# p128relay.net
KiCad netlist of a schematic drawn in EAGLE
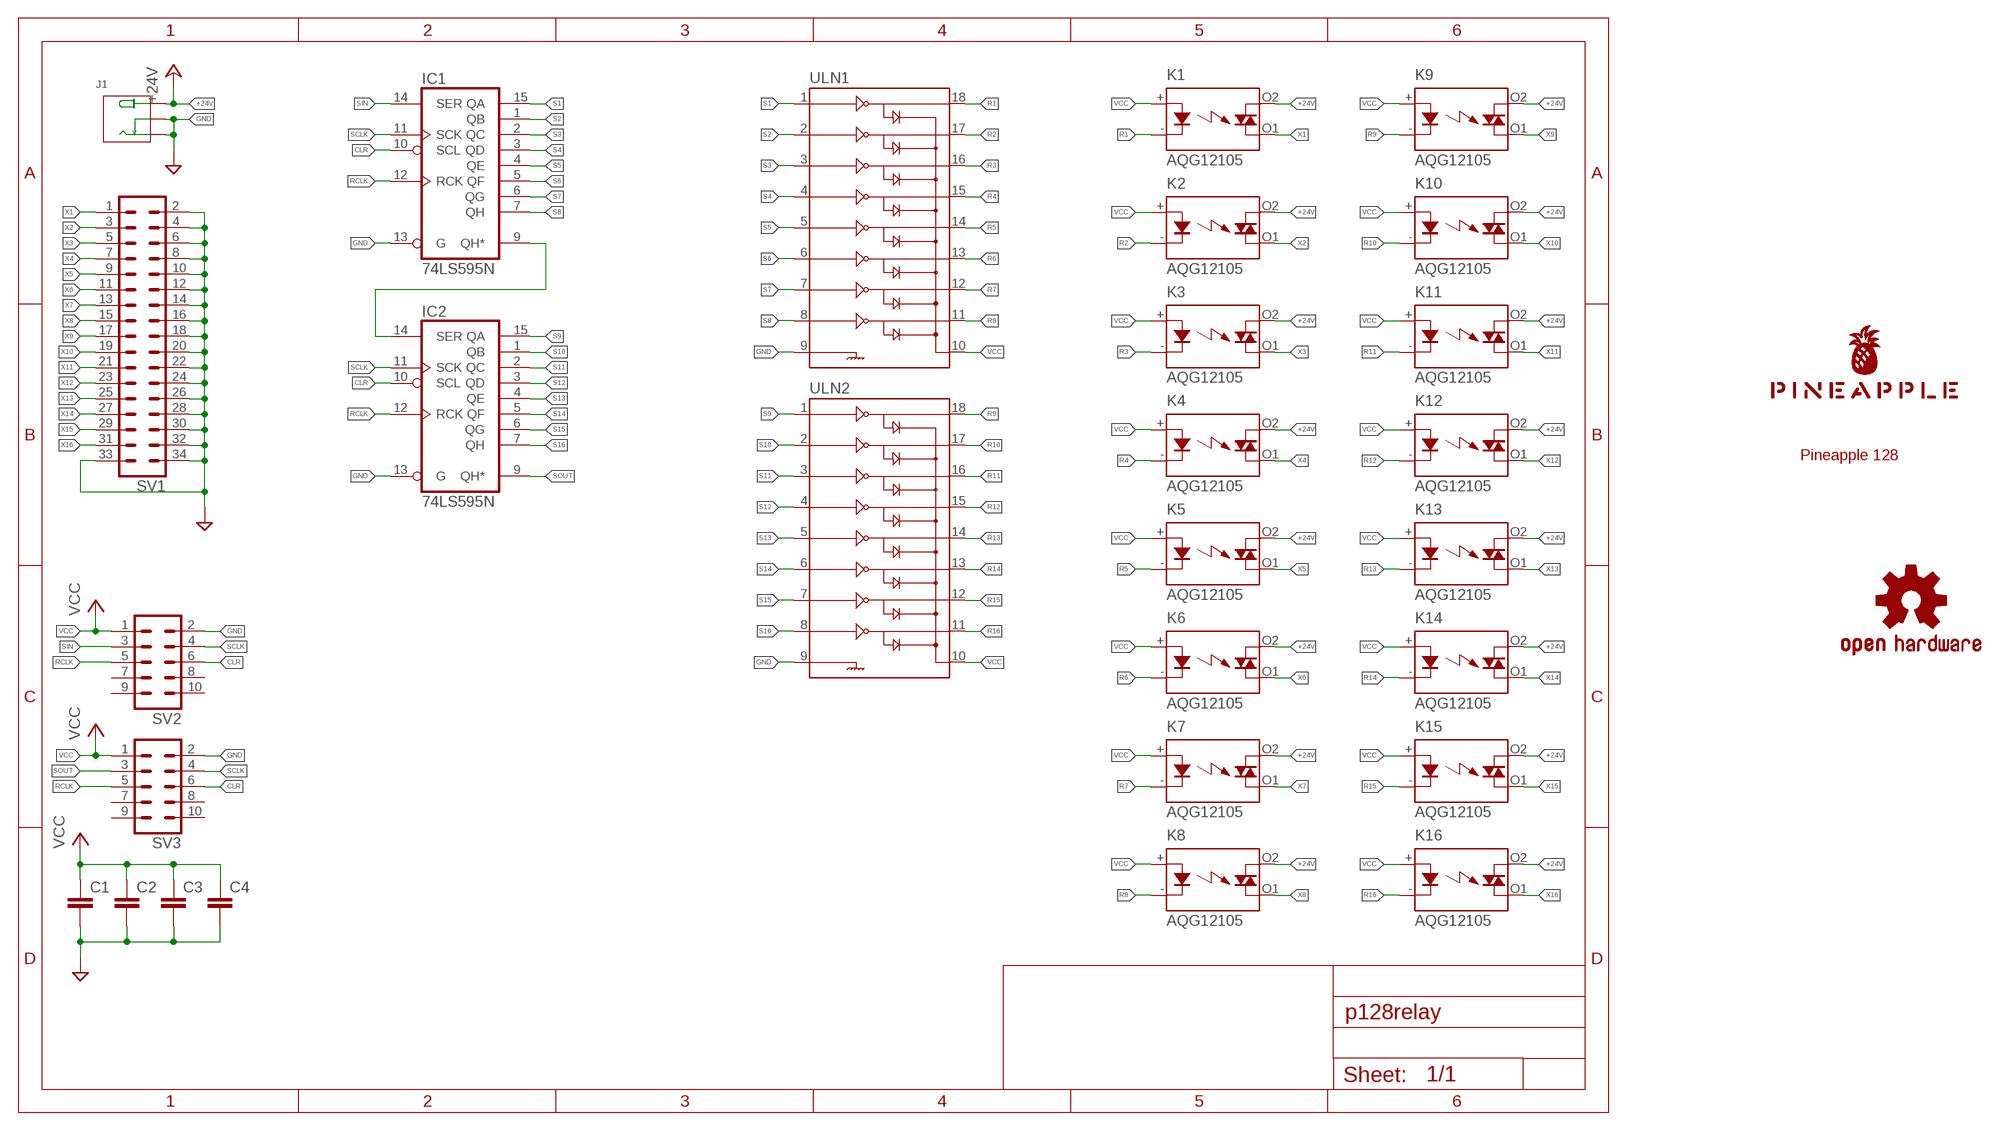
[diagram p0: schematic, sheet 1]

(export (version "E")
  (design (tool "Eeschema 10.0.6"))
  (components
    (comp (ref "C1")
      (value "C-EU025-024X044")
      (footprint "eagle-import:C025-024X044")
      (libsource (lib "eagle-import") (part "C-EU025-024X044"))
    )
    (comp (ref "C2")
      (value "C-EU025-024X044")
      (footprint "eagle-import:C025-024X044")
      (libsource (lib "eagle-import") (part "C-EU025-024X044"))
    )
    (comp (ref "C3")
      (value "C-EU025-024X044")
      (footprint "eagle-import:C025-024X044")
      (libsource (lib "eagle-import") (part "C-EU025-024X044"))
    )
    (comp (ref "C4")
      (value "C-EU025-024X044")
      (footprint "eagle-import:C025-024X044")
      (libsource (lib "eagle-import") (part "C-EU025-024X044"))
    )
    (comp (ref "IC1")
      (value "74LS595N")
      (footprint "eagle-import:DIL16")
      (libsource (lib "eagle-import") (part "74595NLS"))
    )
    (comp (ref "IC2")
      (value "74LS595N")
      (footprint "eagle-import:DIL16")
      (libsource (lib "eagle-import") (part "74595NLS"))
    )
    (comp (ref "J1")
      (value "JACK-DC-005'DC-005'")
      (footprint "eagle-import:3P-L14.2_W11.0_H9.0MM")
      (libsource (lib "eagle-import") (part "JACK-DC-005'DC-005'"))
    )
    (comp (ref "K1")
      (value "AQG12105")
      (footprint "eagle-import:AQG")
      (fields (field (name "MF") "AROMAT/ MATSUSHITA"))
      (libsource (lib "eagle-import") (part "AQG12105"))
    )
    (comp (ref "K2")
      (value "AQG12105")
      (footprint "eagle-import:AQG")
      (fields (field (name "MF") "AROMAT/ MATSUSHITA"))
      (libsource (lib "eagle-import") (part "AQG12105"))
    )
    (comp (ref "K3")
      (value "AQG12105")
      (footprint "eagle-import:AQG")
      (fields (field (name "MF") "AROMAT/ MATSUSHITA"))
      (libsource (lib "eagle-import") (part "AQG12105"))
    )
    (comp (ref "K4")
      (value "AQG12105")
      (footprint "eagle-import:AQG")
      (fields (field (name "MF") "AROMAT/ MATSUSHITA"))
      (libsource (lib "eagle-import") (part "AQG12105"))
    )
    (comp (ref "K5")
      (value "AQG12105")
      (footprint "eagle-import:AQG")
      (fields (field (name "MF") "AROMAT/ MATSUSHITA"))
      (libsource (lib "eagle-import") (part "AQG12105"))
    )
    (comp (ref "K6")
      (value "AQG12105")
      (footprint "eagle-import:AQG")
      (fields (field (name "MF") "AROMAT/ MATSUSHITA"))
      (libsource (lib "eagle-import") (part "AQG12105"))
    )
    (comp (ref "K7")
      (value "AQG12105")
      (footprint "eagle-import:AQG")
      (fields (field (name "MF") "AROMAT/ MATSUSHITA"))
      (libsource (lib "eagle-import") (part "AQG12105"))
    )
    (comp (ref "K8")
      (value "AQG12105")
      (footprint "eagle-import:AQG")
      (fields (field (name "MF") "AROMAT/ MATSUSHITA"))
      (libsource (lib "eagle-import") (part "AQG12105"))
    )
    (comp (ref "K9")
      (value "AQG12105")
      (footprint "eagle-import:AQG")
      (fields (field (name "MF") "AROMAT/ MATSUSHITA"))
      (libsource (lib "eagle-import") (part "AQG12105"))
    )
    (comp (ref "K10")
      (value "AQG12105")
      (footprint "eagle-import:AQG")
      (fields (field (name "MF") "AROMAT/ MATSUSHITA"))
      (libsource (lib "eagle-import") (part "AQG12105"))
    )
    (comp (ref "K11")
      (value "AQG12105")
      (footprint "eagle-import:AQG")
      (fields (field (name "MF") "AROMAT/ MATSUSHITA"))
      (libsource (lib "eagle-import") (part "AQG12105"))
    )
    (comp (ref "K12")
      (value "AQG12105")
      (footprint "eagle-import:AQG")
      (fields (field (name "MF") "AROMAT/ MATSUSHITA"))
      (libsource (lib "eagle-import") (part "AQG12105"))
    )
    (comp (ref "K13")
      (value "AQG12105")
      (footprint "eagle-import:AQG")
      (fields (field (name "MF") "AROMAT/ MATSUSHITA"))
      (libsource (lib "eagle-import") (part "AQG12105"))
    )
    (comp (ref "K14")
      (value "AQG12105")
      (footprint "eagle-import:AQG")
      (fields (field (name "MF") "AROMAT/ MATSUSHITA"))
      (libsource (lib "eagle-import") (part "AQG12105"))
    )
    (comp (ref "K15")
      (value "AQG12105")
      (footprint "eagle-import:AQG")
      (fields (field (name "MF") "AROMAT/ MATSUSHITA"))
      (libsource (lib "eagle-import") (part "AQG12105"))
    )
    (comp (ref "K16")
      (value "AQG12105")
      (footprint "eagle-import:AQG")
      (fields (field (name "MF") "AROMAT/ MATSUSHITA"))
      (libsource (lib "eagle-import") (part "AQG12105"))
    )
    (comp (ref "LOGO1")
      (value "OSHW-LOGOS-COPPER")
      (footprint "eagle-import:OSHW-LOGO-S_COPPER")
      (libsource (lib "eagle-import") (part "OSHW-LOGOS-COPPER"))
    )
    (comp (ref "SV1")
      (value "ML34L")
      (footprint "eagle-import:ML34L")
      (libsource (lib "eagle-import") (part "ML34L"))
    )
    (comp (ref "SV2")
      (value "ML10L")
      (footprint "eagle-import:ML10L")
      (libsource (lib "eagle-import") (part "ML10L"))
    )
    (comp (ref "SV3")
      (value "ML10L")
      (footprint "eagle-import:ML10L")
      (libsource (lib "eagle-import") (part "ML10L"))
    )
    (comp (ref "U$1")
      (value "PINEAPPLE450_SILK")
      (footprint "eagle-import:PINEAPPLE450_SILK")
      (libsource (lib "eagle-import") (part "PINEAPPLE450_SILK"))
    )
    (comp (ref "ULN1")
      (value "ULN2803DIP")
      (footprint "eagle-import:DIL18")
      (libsource (lib "eagle-import") (part "ULN2803DIP"))
    )
    (comp (ref "ULN2")
      (value "ULN2803DIP")
      (footprint "eagle-import:DIL18")
      (libsource (lib "eagle-import") (part "ULN2803DIP"))
    )
  )
  (nets
    (net (code "1") (name "+24V") (class "Default")
      (node (ref "J1") (pin "+") (pinfunction "+_+") (pintype "bidirectional"))
      (node (ref "K1") (pin "O2") (pinfunction "DS1_O2") (pintype "passive"))
      (node (ref "K10") (pin "O2") (pinfunction "DS1_O2") (pintype "passive"))
      (node (ref "K11") (pin "O2") (pinfunction "DS1_O2") (pintype "passive"))
      (node (ref "K12") (pin "O2") (pinfunction "DS1_O2") (pintype "passive"))
      (node (ref "K13") (pin "O2") (pinfunction "DS1_O2") (pintype "passive"))
      (node (ref "K14") (pin "O2") (pinfunction "DS1_O2") (pintype "passive"))
      (node (ref "K15") (pin "O2") (pinfunction "DS1_O2") (pintype "passive"))
      (node (ref "K16") (pin "O2") (pinfunction "DS1_O2") (pintype "passive"))
      (node (ref "K2") (pin "O2") (pinfunction "DS1_O2") (pintype "passive"))
      (node (ref "K3") (pin "O2") (pinfunction "DS1_O2") (pintype "passive"))
      (node (ref "K4") (pin "O2") (pinfunction "DS1_O2") (pintype "passive"))
      (node (ref "K5") (pin "O2") (pinfunction "DS1_O2") (pintype "passive"))
      (node (ref "K6") (pin "O2") (pinfunction "DS1_O2") (pintype "passive"))
      (node (ref "K7") (pin "O2") (pinfunction "DS1_O2") (pintype "passive"))
      (node (ref "K8") (pin "O2") (pinfunction "DS1_O2") (pintype "passive"))
      (node (ref "K9") (pin "O2") (pinfunction "DS1_O2") (pintype "passive"))
    )
    (net (code "2") (name "CLR") (class "Default")
      (node (ref "IC1") (pin "10") (pinfunction "SCL_10") (pintype "input"))
      (node (ref "IC2") (pin "10") (pinfunction "SCL_10") (pintype "input"))
      (node (ref "SV2") (pin "6") (pinfunction "6_6") (pintype "passive"))
      (node (ref "SV3") (pin "6") (pinfunction "6_6") (pintype "passive"))
    )
    (net (code "3") (name "GND") (class "Default")
      (node (ref "C1") (pin "2") (pinfunction "2_2") (pintype "passive"))
      (node (ref "C2") (pin "2") (pinfunction "2_2") (pintype "passive"))
      (node (ref "C3") (pin "2") (pinfunction "2_2") (pintype "passive"))
      (node (ref "C4") (pin "2") (pinfunction "2_2") (pintype "passive"))
      (node (ref "IC1") (pin "13") (pinfunction "G_13") (pintype "input"))
      (node (ref "IC2") (pin "13") (pinfunction "G_13") (pintype "input"))
      (node (ref "J1") (pin "-1") (pinfunction "-_-1") (pintype "bidirectional"))
      (node (ref "J1") (pin "-2") (pinfunction "CDN_-2") (pintype "bidirectional"))
      (node (ref "SV1") (pin "10") (pinfunction "10_10") (pintype "passive"))
      (node (ref "SV1") (pin "12") (pinfunction "12_12") (pintype "passive"))
      (node (ref "SV1") (pin "14") (pinfunction "14_14") (pintype "passive"))
      (node (ref "SV1") (pin "16") (pinfunction "16_16") (pintype "passive"))
      (node (ref "SV1") (pin "18") (pinfunction "18_18") (pintype "passive"))
      (node (ref "SV1") (pin "2") (pinfunction "2_2") (pintype "passive"))
      (node (ref "SV1") (pin "20") (pinfunction "20_20") (pintype "passive"))
      (node (ref "SV1") (pin "22") (pinfunction "22_22") (pintype "passive"))
      (node (ref "SV1") (pin "24") (pinfunction "24_24") (pintype "passive"))
      (node (ref "SV1") (pin "26") (pinfunction "26_26") (pintype "passive"))
      (node (ref "SV1") (pin "28") (pinfunction "28_28") (pintype "passive"))
      (node (ref "SV1") (pin "30") (pinfunction "30_30") (pintype "passive"))
      (node (ref "SV1") (pin "32") (pinfunction "32_32") (pintype "passive"))
      (node (ref "SV1") (pin "33") (pinfunction "33_33") (pintype "passive"))
      (node (ref "SV1") (pin "34") (pinfunction "34_34") (pintype "passive"))
      (node (ref "SV1") (pin "4") (pinfunction "4_4") (pintype "passive"))
      (node (ref "SV1") (pin "6") (pinfunction "6_6") (pintype "passive"))
      (node (ref "SV1") (pin "8") (pinfunction "8_8") (pintype "passive"))
      (node (ref "SV2") (pin "2") (pinfunction "2_2") (pintype "passive"))
      (node (ref "SV3") (pin "2") (pinfunction "2_2") (pintype "passive"))
      (node (ref "ULN1") (pin "9") (pinfunction "9_9") (pintype "bidirectional"))
      (node (ref "ULN2") (pin "9") (pinfunction "9_9") (pintype "bidirectional"))
    )
    (net (code "4") (name "Net-(IC1A-QH*)") (class "Default")
      (node (ref "IC1") (pin "9") (pinfunction "QH*_9") (pintype "tri_state"))
      (node (ref "IC2") (pin "14") (pinfunction "SER_14") (pintype "input"))
    )
    (net (code "5") (name "R1") (class "Default")
      (node (ref "K1") (pin "-") (pinfunction "K_-") (pintype "passive"))
      (node (ref "ULN1") (pin "18") (pinfunction "18_18") (pintype "bidirectional"))
    )
    (net (code "6") (name "R2") (class "Default")
      (node (ref "K2") (pin "-") (pinfunction "K_-") (pintype "passive"))
      (node (ref "ULN1") (pin "17") (pinfunction "17_17") (pintype "bidirectional"))
    )
    (net (code "7") (name "R3") (class "Default")
      (node (ref "K3") (pin "-") (pinfunction "K_-") (pintype "passive"))
      (node (ref "ULN1") (pin "16") (pinfunction "16_16") (pintype "bidirectional"))
    )
    (net (code "8") (name "R4") (class "Default")
      (node (ref "K4") (pin "-") (pinfunction "K_-") (pintype "passive"))
      (node (ref "ULN1") (pin "15") (pinfunction "15_15") (pintype "bidirectional"))
    )
    (net (code "9") (name "R5") (class "Default")
      (node (ref "K5") (pin "-") (pinfunction "K_-") (pintype "passive"))
      (node (ref "ULN1") (pin "14") (pinfunction "14_14") (pintype "bidirectional"))
    )
    (net (code "10") (name "R6") (class "Default")
      (node (ref "K6") (pin "-") (pinfunction "K_-") (pintype "passive"))
      (node (ref "ULN1") (pin "13") (pinfunction "13_13") (pintype "bidirectional"))
    )
    (net (code "11") (name "R7") (class "Default")
      (node (ref "K7") (pin "-") (pinfunction "K_-") (pintype "passive"))
      (node (ref "ULN1") (pin "12") (pinfunction "12_12") (pintype "bidirectional"))
    )
    (net (code "12") (name "R8") (class "Default")
      (node (ref "K8") (pin "-") (pinfunction "K_-") (pintype "passive"))
      (node (ref "ULN1") (pin "11") (pinfunction "11_11") (pintype "bidirectional"))
    )
    (net (code "13") (name "R9") (class "Default")
      (node (ref "K9") (pin "-") (pinfunction "K_-") (pintype "passive"))
      (node (ref "ULN2") (pin "18") (pinfunction "18_18") (pintype "bidirectional"))
    )
    (net (code "14") (name "R10") (class "Default")
      (node (ref "K10") (pin "-") (pinfunction "K_-") (pintype "passive"))
      (node (ref "ULN2") (pin "17") (pinfunction "17_17") (pintype "bidirectional"))
    )
    (net (code "15") (name "R11") (class "Default")
      (node (ref "K11") (pin "-") (pinfunction "K_-") (pintype "passive"))
      (node (ref "ULN2") (pin "16") (pinfunction "16_16") (pintype "bidirectional"))
    )
    (net (code "16") (name "R12") (class "Default")
      (node (ref "K12") (pin "-") (pinfunction "K_-") (pintype "passive"))
      (node (ref "ULN2") (pin "15") (pinfunction "15_15") (pintype "bidirectional"))
    )
    (net (code "17") (name "R13") (class "Default")
      (node (ref "K13") (pin "-") (pinfunction "K_-") (pintype "passive"))
      (node (ref "ULN2") (pin "14") (pinfunction "14_14") (pintype "bidirectional"))
    )
    (net (code "18") (name "R14") (class "Default")
      (node (ref "K14") (pin "-") (pinfunction "K_-") (pintype "passive"))
      (node (ref "ULN2") (pin "13") (pinfunction "13_13") (pintype "bidirectional"))
    )
    (net (code "19") (name "R15") (class "Default")
      (node (ref "K15") (pin "-") (pinfunction "K_-") (pintype "passive"))
      (node (ref "ULN2") (pin "12") (pinfunction "12_12") (pintype "bidirectional"))
    )
    (net (code "20") (name "R16") (class "Default")
      (node (ref "K16") (pin "-") (pinfunction "K_-") (pintype "passive"))
      (node (ref "ULN2") (pin "11") (pinfunction "11_11") (pintype "bidirectional"))
    )
    (net (code "21") (name "RCLK") (class "Default")
      (node (ref "IC1") (pin "12") (pinfunction "RCK_12") (pintype "input"))
      (node (ref "IC2") (pin "12") (pinfunction "RCK_12") (pintype "input"))
      (node (ref "SV2") (pin "5") (pinfunction "5_5") (pintype "passive"))
      (node (ref "SV3") (pin "5") (pinfunction "5_5") (pintype "passive"))
    )
    (net (code "22") (name "S1") (class "Default")
      (node (ref "IC1") (pin "15") (pinfunction "QA_15") (pintype "tri_state"))
      (node (ref "ULN1") (pin "1") (pinfunction "1_1") (pintype "bidirectional"))
    )
    (net (code "23") (name "S2") (class "Default")
      (node (ref "IC1") (pin "1") (pinfunction "QB_1") (pintype "tri_state"))
      (node (ref "ULN1") (pin "2") (pinfunction "2_2") (pintype "bidirectional"))
    )
    (net (code "24") (name "S3") (class "Default")
      (node (ref "IC1") (pin "2") (pinfunction "QC_2") (pintype "tri_state"))
      (node (ref "ULN1") (pin "3") (pinfunction "3_3") (pintype "bidirectional"))
    )
    (net (code "25") (name "S4") (class "Default")
      (node (ref "IC1") (pin "3") (pinfunction "QD_3") (pintype "tri_state"))
      (node (ref "ULN1") (pin "4") (pinfunction "4_4") (pintype "bidirectional"))
    )
    (net (code "26") (name "S5") (class "Default")
      (node (ref "IC1") (pin "4") (pinfunction "QE_4") (pintype "tri_state"))
      (node (ref "ULN1") (pin "5") (pinfunction "5_5") (pintype "bidirectional"))
    )
    (net (code "27") (name "S6") (class "Default")
      (node (ref "IC1") (pin "5") (pinfunction "QF_5") (pintype "tri_state"))
      (node (ref "ULN1") (pin "6") (pinfunction "6_6") (pintype "bidirectional"))
    )
    (net (code "28") (name "S7") (class "Default")
      (node (ref "IC1") (pin "6") (pinfunction "QG_6") (pintype "tri_state"))
      (node (ref "ULN1") (pin "7") (pinfunction "7_7") (pintype "bidirectional"))
    )
    (net (code "29") (name "S8") (class "Default")
      (node (ref "IC1") (pin "7") (pinfunction "QH_7") (pintype "tri_state"))
      (node (ref "ULN1") (pin "8") (pinfunction "8_8") (pintype "bidirectional"))
    )
    (net (code "30") (name "S9") (class "Default")
      (node (ref "IC2") (pin "15") (pinfunction "QA_15") (pintype "tri_state"))
      (node (ref "ULN2") (pin "1") (pinfunction "1_1") (pintype "bidirectional"))
    )
    (net (code "31") (name "S10") (class "Default")
      (node (ref "IC2") (pin "1") (pinfunction "QB_1") (pintype "tri_state"))
      (node (ref "ULN2") (pin "2") (pinfunction "2_2") (pintype "bidirectional"))
    )
    (net (code "32") (name "S11") (class "Default")
      (node (ref "IC2") (pin "2") (pinfunction "QC_2") (pintype "tri_state"))
      (node (ref "ULN2") (pin "3") (pinfunction "3_3") (pintype "bidirectional"))
    )
    (net (code "33") (name "S12") (class "Default")
      (node (ref "IC2") (pin "3") (pinfunction "QD_3") (pintype "tri_state"))
      (node (ref "ULN2") (pin "4") (pinfunction "4_4") (pintype "bidirectional"))
    )
    (net (code "34") (name "S13") (class "Default")
      (node (ref "IC2") (pin "4") (pinfunction "QE_4") (pintype "tri_state"))
      (node (ref "ULN2") (pin "5") (pinfunction "5_5") (pintype "bidirectional"))
    )
    (net (code "35") (name "S14") (class "Default")
      (node (ref "IC2") (pin "5") (pinfunction "QF_5") (pintype "tri_state"))
      (node (ref "ULN2") (pin "6") (pinfunction "6_6") (pintype "bidirectional"))
    )
    (net (code "36") (name "S15") (class "Default")
      (node (ref "IC2") (pin "6") (pinfunction "QG_6") (pintype "tri_state"))
      (node (ref "ULN2") (pin "7") (pinfunction "7_7") (pintype "bidirectional"))
    )
    (net (code "37") (name "S16") (class "Default")
      (node (ref "IC2") (pin "7") (pinfunction "QH_7") (pintype "tri_state"))
      (node (ref "ULN2") (pin "8") (pinfunction "8_8") (pintype "bidirectional"))
    )
    (net (code "38") (name "SCLK") (class "Default")
      (node (ref "IC1") (pin "11") (pinfunction "SCK_11") (pintype "input"))
      (node (ref "IC2") (pin "11") (pinfunction "SCK_11") (pintype "input"))
      (node (ref "SV2") (pin "4") (pinfunction "4_4") (pintype "passive"))
      (node (ref "SV3") (pin "4") (pinfunction "4_4") (pintype "passive"))
    )
    (net (code "39") (name "SIN") (class "Default")
      (node (ref "IC1") (pin "14") (pinfunction "SER_14") (pintype "input"))
      (node (ref "SV2") (pin "3") (pinfunction "3_3") (pintype "passive"))
    )
    (net (code "40") (name "SOUT") (class "Default")
      (node (ref "IC2") (pin "9") (pinfunction "QH*_9") (pintype "tri_state"))
      (node (ref "SV3") (pin "3") (pinfunction "3_3") (pintype "passive"))
    )
    (net (code "41") (name "VCC") (class "Default")
      (node (ref "C1") (pin "1") (pinfunction "1_1") (pintype "passive"))
      (node (ref "C2") (pin "1") (pinfunction "1_1") (pintype "passive"))
      (node (ref "C3") (pin "1") (pinfunction "1_1") (pintype "passive"))
      (node (ref "C4") (pin "1") (pinfunction "1_1") (pintype "passive"))
      (node (ref "K1") (pin "+") (pinfunction "A_+") (pintype "passive"))
      (node (ref "K10") (pin "+") (pinfunction "A_+") (pintype "passive"))
      (node (ref "K11") (pin "+") (pinfunction "A_+") (pintype "passive"))
      (node (ref "K12") (pin "+") (pinfunction "A_+") (pintype "passive"))
      (node (ref "K13") (pin "+") (pinfunction "A_+") (pintype "passive"))
      (node (ref "K14") (pin "+") (pinfunction "A_+") (pintype "passive"))
      (node (ref "K15") (pin "+") (pinfunction "A_+") (pintype "passive"))
      (node (ref "K16") (pin "+") (pinfunction "A_+") (pintype "passive"))
      (node (ref "K2") (pin "+") (pinfunction "A_+") (pintype "passive"))
      (node (ref "K3") (pin "+") (pinfunction "A_+") (pintype "passive"))
      (node (ref "K4") (pin "+") (pinfunction "A_+") (pintype "passive"))
      (node (ref "K5") (pin "+") (pinfunction "A_+") (pintype "passive"))
      (node (ref "K6") (pin "+") (pinfunction "A_+") (pintype "passive"))
      (node (ref "K7") (pin "+") (pinfunction "A_+") (pintype "passive"))
      (node (ref "K8") (pin "+") (pinfunction "A_+") (pintype "passive"))
      (node (ref "K9") (pin "+") (pinfunction "A_+") (pintype "passive"))
      (node (ref "SV2") (pin "1") (pinfunction "1_1") (pintype "passive"))
      (node (ref "SV3") (pin "1") (pinfunction "1_1") (pintype "passive"))
      (node (ref "ULN1") (pin "10") (pinfunction "10_10") (pintype "bidirectional"))
      (node (ref "ULN2") (pin "10") (pinfunction "10_10") (pintype "bidirectional"))
    )
    (net (code "42") (name "X1") (class "Default")
      (node (ref "K1") (pin "O1") (pinfunction "DS2_O1") (pintype "passive"))
      (node (ref "SV1") (pin "1") (pinfunction "1_1") (pintype "passive"))
    )
    (net (code "43") (name "X2") (class "Default")
      (node (ref "K2") (pin "O1") (pinfunction "DS2_O1") (pintype "passive"))
      (node (ref "SV1") (pin "3") (pinfunction "3_3") (pintype "passive"))
    )
    (net (code "44") (name "X3") (class "Default")
      (node (ref "K3") (pin "O1") (pinfunction "DS2_O1") (pintype "passive"))
      (node (ref "SV1") (pin "5") (pinfunction "5_5") (pintype "passive"))
    )
    (net (code "45") (name "X4") (class "Default")
      (node (ref "K4") (pin "O1") (pinfunction "DS2_O1") (pintype "passive"))
      (node (ref "SV1") (pin "7") (pinfunction "7_7") (pintype "passive"))
    )
    (net (code "46") (name "X5") (class "Default")
      (node (ref "K5") (pin "O1") (pinfunction "DS2_O1") (pintype "passive"))
      (node (ref "SV1") (pin "9") (pinfunction "9_9") (pintype "passive"))
    )
    (net (code "47") (name "X6") (class "Default")
      (node (ref "K6") (pin "O1") (pinfunction "DS2_O1") (pintype "passive"))
      (node (ref "SV1") (pin "11") (pinfunction "11_11") (pintype "passive"))
    )
    (net (code "48") (name "X7") (class "Default")
      (node (ref "K7") (pin "O1") (pinfunction "DS2_O1") (pintype "passive"))
      (node (ref "SV1") (pin "13") (pinfunction "13_13") (pintype "passive"))
    )
    (net (code "49") (name "X8") (class "Default")
      (node (ref "K8") (pin "O1") (pinfunction "DS2_O1") (pintype "passive"))
      (node (ref "SV1") (pin "15") (pinfunction "15_15") (pintype "passive"))
    )
    (net (code "50") (name "X9") (class "Default")
      (node (ref "K9") (pin "O1") (pinfunction "DS2_O1") (pintype "passive"))
      (node (ref "SV1") (pin "17") (pinfunction "17_17") (pintype "passive"))
    )
    (net (code "51") (name "X10") (class "Default")
      (node (ref "K10") (pin "O1") (pinfunction "DS2_O1") (pintype "passive"))
      (node (ref "SV1") (pin "19") (pinfunction "19_19") (pintype "passive"))
    )
    (net (code "52") (name "X11") (class "Default")
      (node (ref "K11") (pin "O1") (pinfunction "DS2_O1") (pintype "passive"))
      (node (ref "SV1") (pin "21") (pinfunction "21_21") (pintype "passive"))
    )
    (net (code "53") (name "X12") (class "Default")
      (node (ref "K12") (pin "O1") (pinfunction "DS2_O1") (pintype "passive"))
      (node (ref "SV1") (pin "23") (pinfunction "23_23") (pintype "passive"))
    )
    (net (code "54") (name "X13") (class "Default")
      (node (ref "K13") (pin "O1") (pinfunction "DS2_O1") (pintype "passive"))
      (node (ref "SV1") (pin "25") (pinfunction "25_25") (pintype "passive"))
    )
    (net (code "55") (name "X14") (class "Default")
      (node (ref "K14") (pin "O1") (pinfunction "DS2_O1") (pintype "passive"))
      (node (ref "SV1") (pin "27") (pinfunction "27_27") (pintype "passive"))
    )
    (net (code "56") (name "X15") (class "Default")
      (node (ref "K15") (pin "O1") (pinfunction "DS2_O1") (pintype "passive"))
      (node (ref "SV1") (pin "29") (pinfunction "29_29") (pintype "passive"))
    )
    (net (code "57") (name "X16") (class "Default")
      (node (ref "K16") (pin "O1") (pinfunction "DS2_O1") (pintype "passive"))
      (node (ref "SV1") (pin "31") (pinfunction "31_31") (pintype "passive"))
    )
    (net (code "58") (name "unconnected-(SV2-Pad7)") (class "Default")
      (node (ref "SV2") (pin "7") (pinfunction "7_7") (pintype "passive"))
    )
    (net (code "59") (name "unconnected-(SV2-Pad8)") (class "Default")
      (node (ref "SV2") (pin "8") (pinfunction "8_8") (pintype "passive"))
    )
    (net (code "60") (name "unconnected-(SV2-Pad9)") (class "Default")
      (node (ref "SV2") (pin "9") (pinfunction "9_9") (pintype "passive"))
    )
    (net (code "61") (name "unconnected-(SV2-Pad10)") (class "Default")
      (node (ref "SV2") (pin "10") (pinfunction "10_10") (pintype "passive"))
    )
    (net (code "62") (name "unconnected-(SV3-Pad7)") (class "Default")
      (node (ref "SV3") (pin "7") (pinfunction "7_7") (pintype "passive"))
    )
    (net (code "63") (name "unconnected-(SV3-Pad8)") (class "Default")
      (node (ref "SV3") (pin "8") (pinfunction "8_8") (pintype "passive"))
    )
    (net (code "64") (name "unconnected-(SV3-Pad9)") (class "Default")
      (node (ref "SV3") (pin "9") (pinfunction "9_9") (pintype "passive"))
    )
    (net (code "65") (name "unconnected-(SV3-Pad10)") (class "Default")
      (node (ref "SV3") (pin "10") (pinfunction "10_10") (pintype "passive"))
    )
  )
)
